# telemetry-r2.net
KiCad netlist of a schematic drawn in EAGLE
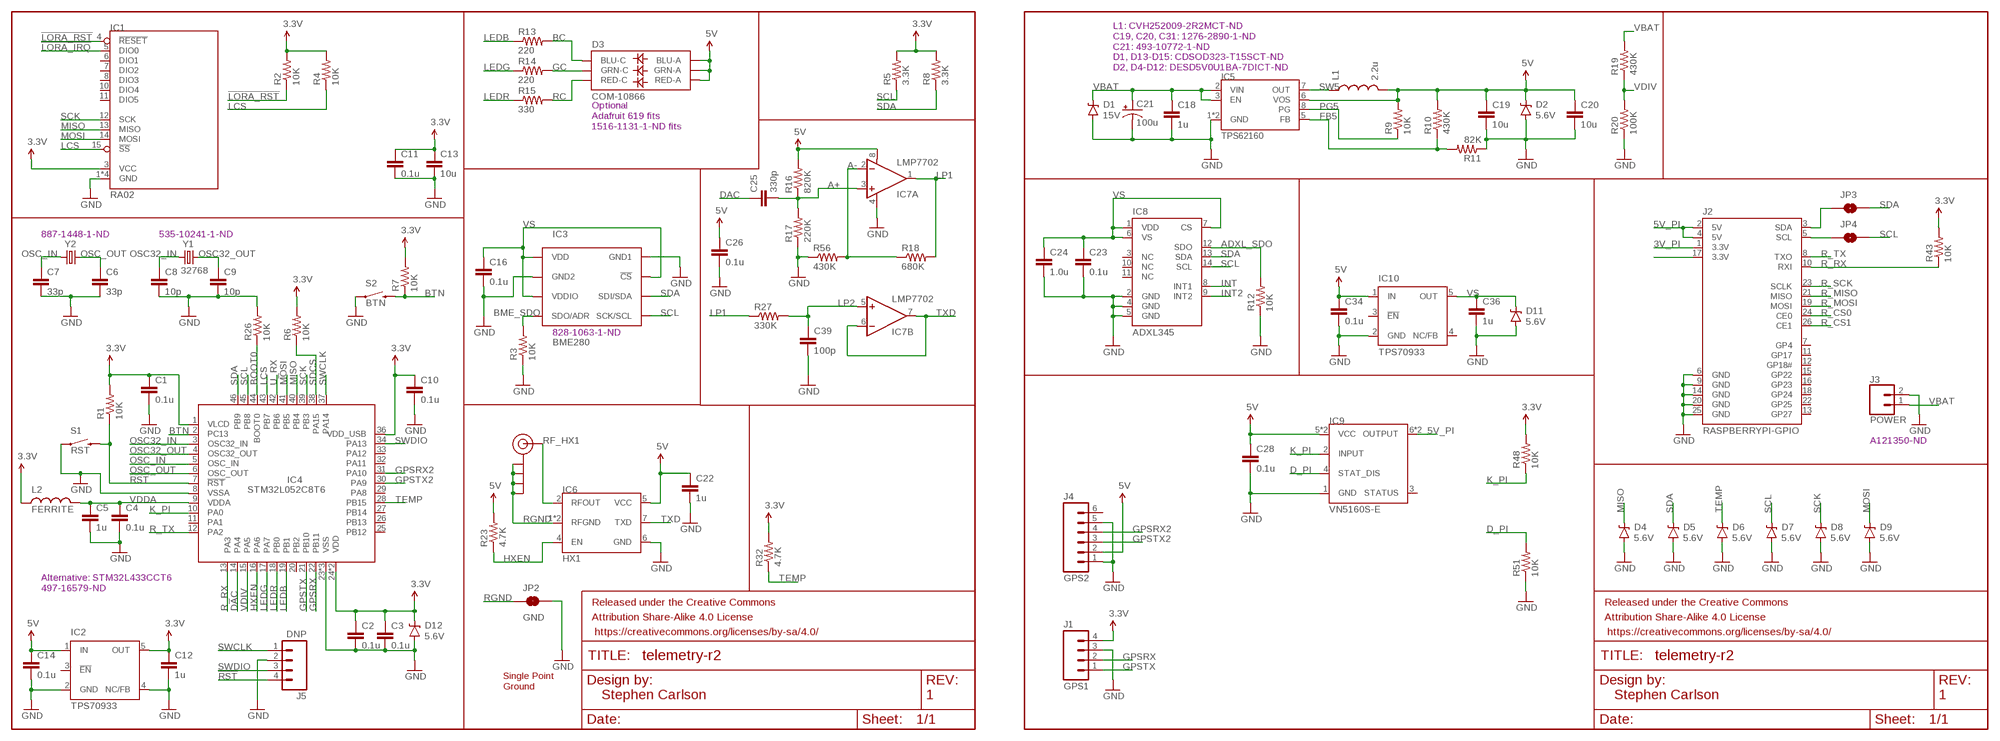
[diagram p0: schematic, sheet 1]

(export (version "E")
  (design (tool "Eeschema 10.0.6"))
  (components
    (comp (ref "C1")
      (value "0.1u")
      (footprint "eagle-import:0805")
      (libsource (lib "eagle-import") (part "CAP0805"))
    )
    (comp (ref "C2")
      (value "0.1u")
      (footprint "eagle-import:0805")
      (libsource (lib "eagle-import") (part "CAP0805"))
    )
    (comp (ref "C3")
      (value "0.1u")
      (footprint "eagle-import:0805")
      (libsource (lib "eagle-import") (part "CAP0805"))
    )
    (comp (ref "C4")
      (value "0.1u")
      (footprint "eagle-import:0805")
      (libsource (lib "eagle-import") (part "CAP0805"))
    )
    (comp (ref "C5")
      (value "1u")
      (footprint "eagle-import:0805")
      (libsource (lib "eagle-import") (part "CAP0805"))
    )
    (comp (ref "C6")
      (value "33p")
      (footprint "eagle-import:0805")
      (libsource (lib "eagle-import") (part "CAP0805"))
    )
    (comp (ref "C7")
      (value "33p")
      (footprint "eagle-import:0805")
      (libsource (lib "eagle-import") (part "CAP0805"))
    )
    (comp (ref "C8")
      (value "10p")
      (footprint "eagle-import:0805")
      (libsource (lib "eagle-import") (part "CAP0805"))
    )
    (comp (ref "C9")
      (value "10p")
      (footprint "eagle-import:0805")
      (libsource (lib "eagle-import") (part "CAP0805"))
    )
    (comp (ref "C10")
      (value "0.1u")
      (footprint "eagle-import:0805")
      (libsource (lib "eagle-import") (part "CAP0805"))
    )
    (comp (ref "C11")
      (value "0.1u")
      (footprint "eagle-import:0805")
      (libsource (lib "eagle-import") (part "CAP0805"))
    )
    (comp (ref "C12")
      (value "1u")
      (footprint "eagle-import:0805")
      (libsource (lib "eagle-import") (part "CAP0805"))
    )
    (comp (ref "C13")
      (value "10u")
      (footprint "eagle-import:0805")
      (libsource (lib "eagle-import") (part "CAP0805"))
    )
    (comp (ref "C14")
      (value "0.1u")
      (footprint "eagle-import:0805")
      (libsource (lib "eagle-import") (part "CAP0805"))
    )
    (comp (ref "C16")
      (value "0.1u")
      (footprint "eagle-import:0805")
      (libsource (lib "eagle-import") (part "CAP0805"))
    )
    (comp (ref "C18")
      (value "1u")
      (footprint "eagle-import:0805")
      (libsource (lib "eagle-import") (part "CAP0805"))
    )
    (comp (ref "C19")
      (value "10u")
      (footprint "eagle-import:0805")
      (libsource (lib "eagle-import") (part "CAP0805"))
    )
    (comp (ref "C20")
      (value "10u")
      (footprint "eagle-import:0805")
      (libsource (lib "eagle-import") (part "CAP0805"))
    )
    (comp (ref "C21")
      (value "100u")
      (footprint "eagle-import:PANASONIC_E")
      (libsource (lib "eagle-import") (part "CAP_POLE"))
    )
    (comp (ref "C22")
      (value "1u")
      (footprint "eagle-import:0805")
      (libsource (lib "eagle-import") (part "CAP0805"))
    )
    (comp (ref "C23")
      (value "0.1u")
      (footprint "eagle-import:0805")
      (libsource (lib "eagle-import") (part "CAP0805"))
    )
    (comp (ref "C24")
      (value "1.0u")
      (footprint "eagle-import:0805")
      (libsource (lib "eagle-import") (part "CAP0805"))
    )
    (comp (ref "C25")
      (value "330p")
      (footprint "eagle-import:0805")
      (libsource (lib "eagle-import") (part "CAP0805"))
    )
    (comp (ref "C26")
      (value "0.1u")
      (footprint "eagle-import:0805")
      (libsource (lib "eagle-import") (part "CAP0805"))
    )
    (comp (ref "C28")
      (value "0.1u")
      (footprint "eagle-import:0805")
      (libsource (lib "eagle-import") (part "CAP0805"))
    )
    (comp (ref "C34")
      (value "0.1u")
      (footprint "eagle-import:0805")
      (libsource (lib "eagle-import") (part "CAP0805"))
    )
    (comp (ref "C36")
      (value "1u")
      (footprint "eagle-import:0805")
      (libsource (lib "eagle-import") (part "CAP0805"))
    )
    (comp (ref "C39")
      (value "100p")
      (footprint "eagle-import:0805")
      (libsource (lib "eagle-import") (part "CAP0805"))
    )
    (comp (ref "D1")
      (value "15V")
      (footprint "eagle-import:SOD-323")
      (libsource (lib "eagle-import") (part "DIODE-ZENER5.6V"))
    )
    (comp (ref "D2")
      (value "5.6V")
      (footprint "eagle-import:SOD-323")
      (libsource (lib "eagle-import") (part "DIODE-ZENER5.6V"))
    )
    (comp (ref "D3")
      (value "COM-10866")
      (footprint "eagle-import:LED-TRICOLOR-5050")
      (libsource (lib "eagle-import") (part "LED-TRICOLOR-5050NO_IC"))
    )
    (comp (ref "D4")
      (value "5.6V")
      (footprint "eagle-import:SOD-323")
      (libsource (lib "eagle-import") (part "DIODE-ZENER5.6V"))
    )
    (comp (ref "D5")
      (value "5.6V")
      (footprint "eagle-import:SOD-323")
      (libsource (lib "eagle-import") (part "DIODE-ZENER5.6V"))
    )
    (comp (ref "D6")
      (value "5.6V")
      (footprint "eagle-import:SOD-323")
      (libsource (lib "eagle-import") (part "DIODE-ZENER5.6V"))
    )
    (comp (ref "D7")
      (value "5.6V")
      (footprint "eagle-import:SOD-323")
      (libsource (lib "eagle-import") (part "DIODE-ZENER5.6V"))
    )
    (comp (ref "D8")
      (value "5.6V")
      (footprint "eagle-import:SOD-323")
      (libsource (lib "eagle-import") (part "DIODE-ZENER5.6V"))
    )
    (comp (ref "D9")
      (value "5.6V")
      (footprint "eagle-import:SOD-323")
      (libsource (lib "eagle-import") (part "DIODE-ZENER5.6V"))
    )
    (comp (ref "D11")
      (value "5.6V")
      (footprint "eagle-import:SOD-323")
      (libsource (lib "eagle-import") (part "DIODE-ZENER5.6V"))
    )
    (comp (ref "D12")
      (value "5.6V")
      (footprint "eagle-import:SOD-323")
      (libsource (lib "eagle-import") (part "DIODE-ZENER5.6V"))
    )
    (comp (ref "FRAME1")
      (value "FRAME-LETTERNO_PACKAGE")
      (footprint "eagle-import:DUMMY")
      (fields (field (name "DESIGNER") "Nobody"))
      (libsource (lib "eagle-import") (part "FRAME-LETTERNO_PACKAGE"))
    )
    (comp (ref "FRAME2")
      (value "FRAME-LETTERNO_PACKAGE")
      (footprint "eagle-import:DUMMY")
      (fields (field (name "DESIGNER") "Nobody"))
      (libsource (lib "eagle-import") (part "FRAME-LETTERNO_PACKAGE"))
    )
    (comp (ref "IC1")
      (value "RA02")
      (footprint "eagle-import:RA02")
      (libsource (lib "eagle-import") (part "RA02"))
    )
    (comp (ref "IC2")
      (value "TPS70933")
      (footprint "eagle-import:SOT23-DBV")
      (fields (field (name "MF") "TEXAS INSTRUMENTS") (field (name "MPN") "TPS77033DBVT"))
      (libsource (lib "eagle-import") (part "TPS77033"))
    )
    (comp (ref "IC3")
      (value "BME280")
      (footprint "eagle-import:BME280_LGA")
      (libsource (lib "eagle-import") (part "BME280"))
    )
    (comp (ref "IC4")
      (value "STM32L052C8T6")
      (footprint "eagle-import:TQFP48")
      (libsource (lib "eagle-import") (part "STM32L07C"))
    )
    (comp (ref "IC5")
      (value "TPS62160")
      (footprint "eagle-import:MSOP8")
      (libsource (lib "eagle-import") (part "TPS62160"))
    )
    (comp (ref "IC6")
      (value "HX1")
      (footprint "eagle-import:HX1")
      (libsource (lib "eagle-import") (part "HX1"))
    )
    (comp (ref "IC7")
      (value "LMP7702")
      (footprint "eagle-import:SO08")
      (libsource (lib "eagle-import") (part "OPAMP-DUALU"))
    )
    (comp (ref "IC8")
      (value "ADXL345")
      (footprint "eagle-import:LGA14")
      (libsource (lib "eagle-import") (part "ADXL345"))
    )
    (comp (ref "IC9")
      (value "VN5160S-E")
      (footprint "eagle-import:SO8")
      (libsource (lib "eagle-import") (part "VN5160S-E"))
    )
    (comp (ref "IC10")
      (value "TPS70933")
      (footprint "eagle-import:SOT23-DBV")
      (fields (field (name "MF") "TEXAS INSTRUMENTS") (field (name "MPN") "TPS77033DBVT"))
      (libsource (lib "eagle-import") (part "TPS77033"))
    )
    (comp (ref "J1")
      (value "GPS1")
      (footprint "eagle-import:1X04")
      (libsource (lib "eagle-import") (part "M04PTH"))
    )
    (comp (ref "J2")
      (value "RASPBERRYPI-GPIO")
      (footprint "eagle-import:2X13-PI")
      (libsource (lib "eagle-import") (part "RASPBERRYPI-GPIO"))
    )
    (comp (ref "J3")
      (value "POWER")
      (footprint "eagle-import:1X02_SCREW")
      (libsource (lib "eagle-import") (part "1X02"))
    )
    (comp (ref "J4")
      (value "GPS2")
      (footprint "eagle-import:1X06-1MM")
      (libsource (lib "eagle-import") (part "M06SMD-1MM"))
    )
    (comp (ref "J5")
      (value "DNP")
      (footprint "eagle-import:1X04_LOCK")
      (libsource (lib "eagle-import") (part "M04LOCK"))
    )
    (comp (ref "J6")
      (value "SMA_EDGE")
      (footprint "eagle-import:SMA-EDGE")
      (libsource (lib "eagle-import") (part "SMA_EDGE"))
    )
    (comp (ref "JP2")
      (value "GND")
      (footprint "eagle-import:PAD-JUMPER-2-NC_BY_TRACE_YES_SILK")
      (libsource (lib "eagle-import") (part "JUMPER-PAD-2-NC_BY_TRACE"))
    )
    (comp (ref "JP3")
      (value "SDA")
      (footprint "eagle-import:SMT-JUMPER_2_NO_SILK")
      (libsource (lib "eagle-import") (part "JUMPER-SMT_2_NO_SILK"))
    )
    (comp (ref "JP4")
      (value "SCL")
      (footprint "eagle-import:SMT-JUMPER_2_NO_SILK")
      (libsource (lib "eagle-import") (part "JUMPER-SMT_2_NO_SILK"))
    )
    (comp (ref "L1")
      (value "2.2u")
      (footprint "eagle-import:1008")
      (libsource (lib "eagle-import") (part "INDUCTOR1008"))
    )
    (comp (ref "L2")
      (value "FERRITE")
      (footprint "eagle-import:1206")
      (libsource (lib "eagle-import") (part "INDUCTOR1206"))
    )
    (comp (ref "R1")
      (value "10K")
      (footprint "eagle-import:0805")
      (libsource (lib "eagle-import") (part "RESISTOR0805-RES"))
    )
    (comp (ref "R2")
      (value "10K")
      (footprint "eagle-import:0805")
      (libsource (lib "eagle-import") (part "RESISTOR0805-RES"))
    )
    (comp (ref "R3")
      (value "10K")
      (footprint "eagle-import:0805")
      (libsource (lib "eagle-import") (part "RESISTOR0805-RES"))
    )
    (comp (ref "R4")
      (value "10K")
      (footprint "eagle-import:0805")
      (libsource (lib "eagle-import") (part "RESISTOR0805-RES"))
    )
    (comp (ref "R5")
      (value "3.3K")
      (footprint "eagle-import:0805")
      (libsource (lib "eagle-import") (part "RESISTOR0805-RES"))
    )
    (comp (ref "R6")
      (value "10K")
      (footprint "eagle-import:0805")
      (libsource (lib "eagle-import") (part "RESISTOR0805-RES"))
    )
    (comp (ref "R7")
      (value "10K")
      (footprint "eagle-import:0805")
      (libsource (lib "eagle-import") (part "RESISTOR0805-RES"))
    )
    (comp (ref "R8")
      (value "3.3K")
      (footprint "eagle-import:0805")
      (libsource (lib "eagle-import") (part "RESISTOR0805-RES"))
    )
    (comp (ref "R9")
      (value "10K")
      (footprint "eagle-import:0805")
      (libsource (lib "eagle-import") (part "RESISTOR0805-RES"))
    )
    (comp (ref "R10")
      (value "430K")
      (footprint "eagle-import:0805")
      (libsource (lib "eagle-import") (part "RESISTOR0805-RES"))
    )
    (comp (ref "R11")
      (value "82K")
      (footprint "eagle-import:0805")
      (libsource (lib "eagle-import") (part "RESISTOR0805-RES"))
    )
    (comp (ref "R12")
      (value "10K")
      (footprint "eagle-import:0805")
      (libsource (lib "eagle-import") (part "RESISTOR0805-RES"))
    )
    (comp (ref "R13")
      (value "220")
      (footprint "eagle-import:0805")
      (libsource (lib "eagle-import") (part "RESISTOR0805-RES"))
    )
    (comp (ref "R14")
      (value "220")
      (footprint "eagle-import:0805")
      (libsource (lib "eagle-import") (part "RESISTOR0805-RES"))
    )
    (comp (ref "R15")
      (value "330")
      (footprint "eagle-import:0805")
      (libsource (lib "eagle-import") (part "RESISTOR0805-RES"))
    )
    (comp (ref "R16")
      (value "820K")
      (footprint "eagle-import:0805")
      (libsource (lib "eagle-import") (part "RESISTOR0805-RES"))
    )
    (comp (ref "R17")
      (value "220K")
      (footprint "eagle-import:0805")
      (libsource (lib "eagle-import") (part "RESISTOR0805-RES"))
    )
    (comp (ref "R18")
      (value "680K")
      (footprint "eagle-import:0805")
      (libsource (lib "eagle-import") (part "RESISTOR0805-RES"))
    )
    (comp (ref "R19")
      (value "430K")
      (footprint "eagle-import:0805")
      (libsource (lib "eagle-import") (part "RESISTOR0805-RES"))
    )
    (comp (ref "R20")
      (value "100K")
      (footprint "eagle-import:0805")
      (libsource (lib "eagle-import") (part "RESISTOR0805-RES"))
    )
    (comp (ref "R23")
      (value "4.7K")
      (footprint "eagle-import:0805")
      (libsource (lib "eagle-import") (part "RESISTOR0805-RES"))
    )
    (comp (ref "R26")
      (value "10K")
      (footprint "eagle-import:0805")
      (libsource (lib "eagle-import") (part "RESISTOR0805-RES"))
    )
    (comp (ref "R27")
      (value "330K")
      (footprint "eagle-import:0805")
      (libsource (lib "eagle-import") (part "RESISTOR0805-RES"))
    )
    (comp (ref "R32")
      (value "4.7K")
      (footprint "eagle-import:0805")
      (libsource (lib "eagle-import") (part "RESISTOR0805-RES"))
    )
    (comp (ref "R43")
      (value "10K")
      (footprint "eagle-import:0805")
      (libsource (lib "eagle-import") (part "RESISTOR0805-RES"))
    )
    (comp (ref "R48")
      (value "10K")
      (footprint "eagle-import:0805")
      (libsource (lib "eagle-import") (part "RESISTOR0805-RES"))
    )
    (comp (ref "R51")
      (value "10K")
      (footprint "eagle-import:0805")
      (libsource (lib "eagle-import") (part "RESISTOR0805-RES"))
    )
    (comp (ref "R56")
      (value "430K")
      (footprint "eagle-import:0805")
      (libsource (lib "eagle-import") (part "RESISTOR0805-RES"))
    )
    (comp (ref "S1")
      (value "RST")
      (footprint "eagle-import:TACTILE-PTH-THIN")
      (libsource (lib "eagle-import") (part "SWITCH"))
    )
    (comp (ref "S2")
      (value "BTN")
      (footprint "eagle-import:TACTILE-PTH-THIN")
      (libsource (lib "eagle-import") (part "SWITCH"))
    )
    (comp (ref "Y1")
      (value "32768")
      (footprint "eagle-import:ABS25")
      (libsource (lib "eagle-import") (part "CRYSTAL"))
    )
    (comp (ref "Y2")
      (value "8M")
      (footprint "eagle-import:CRYSTAL-TXC-7A")
      (libsource (lib "eagle-import") (part "CRYSTALTXC-7A"))
    )
  )
  (nets
    (net (code "1") (name "/3V_PI") (class "Default")
      (node (ref "J2") (pin "1") (pinfunction "3.3V_1") (pintype "power_in"))
    )
    (net (code "2") (name "/5V_PI") (class "Default")
      (node (ref "IC9") (pin "6") (pinfunction "OUTPUT_6") (pintype "passive"))
      (node (ref "IC9") (pin "7") (pinfunction "OUTPUT_7") (pintype "passive"))
      (node (ref "J2") (pin "2") (pinfunction "5V_2") (pintype "power_in"))
      (node (ref "J2") (pin "4") (pinfunction "5V_4") (pintype "power_in"))
    )
    (net (code "3") (name "/A+") (class "Default")
      (node (ref "C25") (pin "2") (pinfunction "2_2") (pintype "passive"))
      (node (ref "IC7") (pin "3") (pinfunction "+IN_3") (pintype "input"))
      (node (ref "R16") (pin "1") (pinfunction "1_1") (pintype "passive"))
      (node (ref "R17") (pin "2") (pinfunction "2_2") (pintype "passive"))
    )
    (net (code "4") (name "/A-") (class "Default")
      (node (ref "IC7") (pin "2") (pinfunction "-IN_2") (pintype "input"))
      (node (ref "R18") (pin "1") (pinfunction "1_1") (pintype "passive"))
      (node (ref "R56") (pin "2") (pinfunction "2_2") (pintype "passive"))
    )
    (net (code "5") (name "/ADXL_SDO") (class "Default")
      (node (ref "IC8") (pin "12") (pinfunction "SDO_12") (pintype "bidirectional"))
      (node (ref "R12") (pin "2") (pinfunction "2_2") (pintype "passive"))
    )
    (net (code "6") (name "/BC") (class "Default")
      (node (ref "D3") (pin "4") (pinfunction "BLU-C_4") (pintype "bidirectional"))
      (node (ref "R13") (pin "2") (pinfunction "2_2") (pintype "passive"))
    )
    (net (code "7") (name "/BME_SDO") (class "Default")
      (node (ref "IC3") (pin "P$5") (pinfunction "SDO/ADR_P$5") (pintype "bidirectional"))
      (node (ref "R3") (pin "2") (pinfunction "2_2") (pintype "passive"))
    )
    (net (code "8") (name "/BOOT0") (class "Default")
      (node (ref "IC4") (pin "44") (pinfunction "BOOT0_44") (pintype "input"))
      (node (ref "R26") (pin "1") (pinfunction "1_1") (pintype "passive"))
    )
    (net (code "9") (name "/BTN") (class "Default")
      (node (ref "IC4") (pin "2") (pinfunction "PC13_2") (pintype "bidirectional"))
      (node (ref "R7") (pin "1") (pinfunction "1_1") (pintype "passive"))
      (node (ref "S2") (pin "2") (pinfunction "2_2") (pintype "passive"))
    )
    (net (code "10") (name "/DAC") (class "Default")
      (node (ref "C25") (pin "1") (pinfunction "1_1") (pintype "passive"))
      (node (ref "IC4") (pin "14") (pinfunction "PA4_14") (pintype "bidirectional"))
    )
    (net (code "11") (name "/D_PI") (class "Default")
      (node (ref "IC9") (pin "4") (pinfunction "STAT_DIS_4") (pintype "input"))
      (node (ref "R51") (pin "2") (pinfunction "2_2") (pintype "passive"))
    )
    (net (code "12") (name "/FB5") (class "Default")
      (node (ref "IC5") (pin "5") (pinfunction "FB_5") (pintype "input"))
      (node (ref "R10") (pin "1") (pinfunction "1_1") (pintype "passive"))
      (node (ref "R11") (pin "2") (pinfunction "2_2") (pintype "passive"))
    )
    (net (code "13") (name "/GC") (class "Default")
      (node (ref "D3") (pin "6") (pinfunction "GRN-C_6") (pintype "bidirectional"))
      (node (ref "R14") (pin "2") (pinfunction "2_2") (pintype "passive"))
    )
    (net (code "14") (name "/GPSRX") (class "Default")
      (node (ref "IC4") (pin "22") (pinfunction "PB11_22") (pintype "bidirectional"))
      (node (ref "J1") (pin "2") (pinfunction "2_2") (pintype "passive"))
    )
    (net (code "15") (name "/GPSRX2") (class "Default")
      (node (ref "IC4") (pin "31") (pinfunction "PA10_31") (pintype "bidirectional"))
      (node (ref "J4") (pin "4") (pinfunction "4_4") (pintype "passive"))
    )
    (net (code "16") (name "/GPSTX") (class "Default")
      (node (ref "IC4") (pin "21") (pinfunction "PB10_21") (pintype "bidirectional"))
      (node (ref "J1") (pin "1") (pinfunction "1_1") (pintype "passive"))
    )
    (net (code "17") (name "/GPSTX2") (class "Default")
      (node (ref "IC4") (pin "30") (pinfunction "PA9_30") (pintype "bidirectional"))
      (node (ref "J4") (pin "3") (pinfunction "3_3") (pintype "passive"))
    )
    (net (code "18") (name "/HXEN") (class "Default")
      (node (ref "IC4") (pin "16") (pinfunction "PA6_16") (pintype "bidirectional"))
      (node (ref "IC6") (pin "4") (pinfunction "EN_4") (pintype "input"))
      (node (ref "R23") (pin "1") (pinfunction "1_1") (pintype "passive"))
    )
    (net (code "19") (name "/INT") (class "Default")
      (node (ref "IC8") (pin "8") (pinfunction "INT1_8") (pintype "bidirectional"))
    )
    (net (code "20") (name "/INT2") (class "Default")
      (node (ref "IC8") (pin "9") (pinfunction "INT2_9") (pintype "bidirectional"))
    )
    (net (code "21") (name "/K_PI") (class "Default")
      (node (ref "IC4") (pin "10") (pinfunction "PA0_10") (pintype "bidirectional"))
      (node (ref "IC9") (pin "2") (pinfunction "INPUT_2") (pintype "input"))
      (node (ref "R48") (pin "1") (pinfunction "1_1") (pintype "passive"))
    )
    (net (code "22") (name "/LCS") (class "Default")
      (node (ref "IC1") (pin "15") (pinfunction "~{SS}_15") (pintype "input"))
      (node (ref "IC4") (pin "43") (pinfunction "PB7_43") (pintype "bidirectional"))
      (node (ref "R4") (pin "1") (pinfunction "1_1") (pintype "passive"))
    )
    (net (code "23") (name "/LEDB") (class "Default")
      (node (ref "IC4") (pin "19") (pinfunction "PB1_19") (pintype "bidirectional"))
      (node (ref "R13") (pin "1") (pinfunction "1_1") (pintype "passive"))
    )
    (net (code "24") (name "/LEDG") (class "Default")
      (node (ref "IC4") (pin "17") (pinfunction "PA7_17") (pintype "bidirectional"))
      (node (ref "R14") (pin "1") (pinfunction "1_1") (pintype "passive"))
    )
    (net (code "25") (name "/LEDR") (class "Default")
      (node (ref "IC4") (pin "18") (pinfunction "PB0_18") (pintype "bidirectional"))
      (node (ref "R15") (pin "1") (pinfunction "1_1") (pintype "passive"))
    )
    (net (code "26") (name "/LP1") (class "Default")
      (node (ref "IC7") (pin "1") (pinfunction "OUT_1") (pintype "output"))
      (node (ref "R18") (pin "2") (pinfunction "2_2") (pintype "passive"))
      (node (ref "R27") (pin "1") (pinfunction "1_1") (pintype "passive"))
    )
    (net (code "27") (name "/LP2") (class "Default")
      (node (ref "C39") (pin "1") (pinfunction "1_1") (pintype "passive"))
      (node (ref "IC7") (pin "5") (pinfunction "+IN_5") (pintype "input"))
      (node (ref "R27") (pin "2") (pinfunction "2_2") (pintype "passive"))
    )
    (net (code "28") (name "/MISO") (class "Default")
      (node (ref "D4") (pin "C") (pinfunction "C_C") (pintype "passive"))
      (node (ref "IC1") (pin "13") (pinfunction "MISO_13") (pintype "output"))
      (node (ref "IC4") (pin "40") (pinfunction "PB4_40") (pintype "bidirectional"))
    )
    (net (code "29") (name "/MOSI") (class "Default")
      (node (ref "D9") (pin "C") (pinfunction "C_C") (pintype "passive"))
      (node (ref "IC1") (pin "14") (pinfunction "MOSI_14") (pintype "input"))
      (node (ref "IC4") (pin "41") (pinfunction "PB5_41") (pintype "bidirectional"))
    )
    (net (code "30") (name "/OSC32_IN") (class "Default")
      (node (ref "C8") (pin "1") (pinfunction "1_1") (pintype "passive"))
      (node (ref "IC4") (pin "3") (pinfunction "OSC32_IN_3") (pintype "bidirectional"))
      (node (ref "Y1") (pin "1") (pinfunction "1_1") (pintype "passive"))
    )
    (net (code "31") (name "/OSC32_OUT") (class "Default")
      (node (ref "C9") (pin "1") (pinfunction "1_1") (pintype "passive"))
      (node (ref "IC4") (pin "4") (pinfunction "OSC32_OUT_4") (pintype "bidirectional"))
      (node (ref "Y1") (pin "4") (pinfunction "2_4") (pintype "passive"))
    )
    (net (code "32") (name "/OSC_IN") (class "Default")
      (node (ref "C7") (pin "1") (pinfunction "1_1") (pintype "passive"))
      (node (ref "IC4") (pin "5") (pinfunction "OSC_IN_5") (pintype "bidirectional"))
      (node (ref "Y2") (pin "P$1") (pinfunction "1_P$1") (pintype "passive"))
    )
    (net (code "33") (name "/OSC_OUT") (class "Default")
      (node (ref "C6") (pin "1") (pinfunction "1_1") (pintype "passive"))
      (node (ref "IC4") (pin "6") (pinfunction "OSC_OUT_6") (pintype "bidirectional"))
      (node (ref "Y2") (pin "P$2") (pinfunction "2_P$2") (pintype "passive"))
    )
    (net (code "34") (name "/PG5") (class "Default")
      (node (ref "IC5") (pin "8") (pinfunction "PG_8") (pintype "open_collector"))
      (node (ref "R9") (pin "1") (pinfunction "1_1") (pintype "passive"))
    )
    (net (code "35") (name "/RC") (class "Default")
      (node (ref "D3") (pin "5") (pinfunction "RED-C_5") (pintype "bidirectional"))
      (node (ref "R15") (pin "2") (pinfunction "2_2") (pintype "passive"))
    )
    (net (code "36") (name "/RF_HX1") (class "Default")
      (node (ref "IC6") (pin "2") (pinfunction "RFOUT_2") (pintype "output"))
      (node (ref "J6") (pin "SIG") (pinfunction "SIGNAL_SIG") (pintype "bidirectional"))
    )
    (net (code "37") (name "/RGND") (class "Default")
      (node (ref "IC6") (pin "1") (pinfunction "RFGND_1") (pintype "power_in"))
      (node (ref "IC6") (pin "3") (pinfunction "RFGND_3") (pintype "power_in"))
      (node (ref "J6") (pin "GND@0") (pinfunction "GND_GND@0") (pintype "bidirectional"))
      (node (ref "J6") (pin "GND@1") (pinfunction "GND_GND@1") (pintype "bidirectional"))
      (node (ref "J6") (pin "GND@2") (pinfunction "GND_GND@2") (pintype "bidirectional"))
      (node (ref "J6") (pin "GND@3") (pinfunction "GND_GND@3") (pintype "bidirectional"))
      (node (ref "JP2") (pin "1") (pinfunction "1_1") (pintype "passive"))
    )
    (net (code "38") (name "/R_CS0") (class "Default")
      (node (ref "J2") (pin "24") (pinfunction "CE0_24") (pintype "output"))
    )
    (net (code "39") (name "/R_CS1") (class "Default")
      (node (ref "J2") (pin "26") (pinfunction "CE1_26") (pintype "output"))
    )
    (net (code "40") (name "/R_MISO") (class "Default")
      (node (ref "J2") (pin "21") (pinfunction "MISO_21") (pintype "input"))
    )
    (net (code "41") (name "/R_MOSI") (class "Default")
      (node (ref "J2") (pin "19") (pinfunction "MOSI_19") (pintype "output"))
    )
    (net (code "42") (name "/R_RX") (class "Default")
      (node (ref "IC4") (pin "13") (pinfunction "PA3_13") (pintype "bidirectional"))
      (node (ref "J2") (pin "10") (pinfunction "RXI_10") (pintype "input"))
      (node (ref "R43") (pin "1") (pinfunction "1_1") (pintype "passive"))
    )
    (net (code "43") (name "/R_SCK") (class "Default")
      (node (ref "J2") (pin "23") (pinfunction "SCLK_23") (pintype "output"))
    )
    (net (code "44") (name "/R_TX") (class "Default")
      (node (ref "IC4") (pin "12") (pinfunction "PA2_12") (pintype "bidirectional"))
      (node (ref "J2") (pin "8") (pinfunction "TXO_8") (pintype "output"))
    )
    (net (code "45") (name "/SCK") (class "Default")
      (node (ref "D8") (pin "C") (pinfunction "C_C") (pintype "passive"))
      (node (ref "IC1") (pin "12") (pinfunction "SCK_12") (pintype "input"))
      (node (ref "IC4") (pin "39") (pinfunction "PB3_39") (pintype "bidirectional"))
    )
    (net (code "46") (name "/SCL") (class "Default")
      (node (ref "D7") (pin "C") (pinfunction "C_C") (pintype "passive"))
      (node (ref "IC3") (pin "P$4") (pinfunction "SCK/SCL_P$4") (pintype "bidirectional"))
      (node (ref "IC4") (pin "45") (pinfunction "PB8_45") (pintype "bidirectional"))
      (node (ref "IC8") (pin "14") (pinfunction "SCL_14") (pintype "bidirectional"))
      (node (ref "JP4") (pin "2") (pinfunction "2_2") (pintype "passive"))
      (node (ref "R5") (pin "1") (pinfunction "1_1") (pintype "passive"))
    )
    (net (code "47") (name "/SDA") (class "Default")
      (node (ref "D5") (pin "C") (pinfunction "C_C") (pintype "passive"))
      (node (ref "IC3") (pin "P$3") (pinfunction "SDI/SDA_P$3") (pintype "bidirectional"))
      (node (ref "IC4") (pin "46") (pinfunction "PB9_46") (pintype "bidirectional"))
      (node (ref "IC8") (pin "13") (pinfunction "SDA_13") (pintype "bidirectional"))
      (node (ref "JP3") (pin "2") (pinfunction "2_2") (pintype "passive"))
      (node (ref "R8") (pin "1") (pinfunction "1_1") (pintype "passive"))
    )
    (net (code "48") (name "/SDCS") (class "Default")
      (node (ref "IC4") (pin "38") (pinfunction "PA15_38") (pintype "bidirectional"))
      (node (ref "R6") (pin "1") (pinfunction "1_1") (pintype "passive"))
    )
    (net (code "49") (name "/SW5") (class "Default")
      (node (ref "IC5") (pin "7") (pinfunction "OUT_7") (pintype "output"))
      (node (ref "L1") (pin "1") (pinfunction "1_1") (pintype "passive"))
    )
    (net (code "50") (name "/SWCLK") (class "Default")
      (node (ref "IC4") (pin "37") (pinfunction "PA14_37") (pintype "bidirectional"))
      (node (ref "J5") (pin "1") (pinfunction "1_1") (pintype "passive"))
    )
    (net (code "51") (name "/SWDIO") (class "Default")
      (node (ref "IC4") (pin "34") (pinfunction "PA13_34") (pintype "bidirectional"))
      (node (ref "J5") (pin "3") (pinfunction "3_3") (pintype "passive"))
    )
    (net (code "52") (name "/TEMP") (class "Default")
      (node (ref "D6") (pin "C") (pinfunction "C_C") (pintype "passive"))
      (node (ref "IC4") (pin "28") (pinfunction "PB15_28") (pintype "bidirectional"))
      (node (ref "R32") (pin "1") (pinfunction "1_1") (pintype "passive"))
    )
    (net (code "53") (name "/TXD") (class "Default")
      (node (ref "IC6") (pin "7") (pinfunction "TXD_7") (pintype "input"))
      (node (ref "IC7") (pin "6") (pinfunction "-IN_6") (pintype "input"))
      (node (ref "IC7") (pin "7") (pinfunction "OUT_7") (pintype "output"))
    )
    (net (code "54") (name "/U_RX") (class "Default")
      (node (ref "IC4") (pin "42") (pinfunction "PB6_42") (pintype "bidirectional"))
    )
    (net (code "55") (name "/VBAT") (class "Default")
      (node (ref "C18") (pin "1") (pinfunction "1_1") (pintype "passive"))
      (node (ref "C21") (pin "+") (pinfunction "+_+") (pintype "passive"))
      (node (ref "D1") (pin "C") (pinfunction "C_C") (pintype "passive"))
      (node (ref "IC5") (pin "2") (pinfunction "VIN_2") (pintype "power_in"))
      (node (ref "IC5") (pin "3") (pinfunction "EN_3") (pintype "input"))
      (node (ref "J3") (pin "1") (pinfunction "1_1") (pintype "passive"))
      (node (ref "R19") (pin "2") (pinfunction "2_2") (pintype "passive"))
    )
    (net (code "56") (name "/VDDA") (class "Default")
      (node (ref "C4") (pin "1") (pinfunction "1_1") (pintype "passive"))
      (node (ref "C5") (pin "1") (pinfunction "1_1") (pintype "passive"))
      (node (ref "IC4") (pin "9") (pinfunction "VDDA_9") (pintype "power_in"))
      (node (ref "L2") (pin "2") (pinfunction "2_2") (pintype "passive"))
    )
    (net (code "57") (name "/VDIV") (class "Default")
      (node (ref "IC4") (pin "15") (pinfunction "PA5_15") (pintype "bidirectional"))
      (node (ref "R19") (pin "1") (pinfunction "1_1") (pintype "passive"))
      (node (ref "R20") (pin "2") (pinfunction "2_2") (pintype "passive"))
    )
    (net (code "58") (name "/VS") (class "Default")
      (node (ref "C16") (pin "1") (pinfunction "1_1") (pintype "passive"))
      (node (ref "C23") (pin "1") (pinfunction "1_1") (pintype "passive"))
      (node (ref "C24") (pin "1") (pinfunction "1_1") (pintype "passive"))
      (node (ref "C36") (pin "1") (pinfunction "1_1") (pintype "passive"))
      (node (ref "D11") (pin "C") (pinfunction "C_C") (pintype "passive"))
      (node (ref "IC10") (pin "5") (pinfunction "OUT_5") (pintype "passive"))
      (node (ref "IC3") (pin "P$2") (pinfunction "~{CS}_P$2") (pintype "bidirectional"))
      (node (ref "IC3") (pin "P$6") (pinfunction "VDDIO_P$6") (pintype "bidirectional"))
      (node (ref "IC3") (pin "P$8") (pinfunction "VDD_P$8") (pintype "bidirectional"))
      (node (ref "IC8") (pin "1") (pinfunction "VDD_1") (pintype "bidirectional"))
      (node (ref "IC8") (pin "6") (pinfunction "VS_6") (pintype "bidirectional"))
      (node (ref "IC8") (pin "7") (pinfunction "CS_7") (pintype "bidirectional"))
    )
    (net (code "59") (name "/~{LORA_IRQ}") (class "Default")
      (node (ref "IC1") (pin "5") (pinfunction "DIO0_5") (pintype "bidirectional"))
    )
    (net (code "60") (name "/~{LORA_RST}") (class "Default")
      (node (ref "IC1") (pin "4") (pinfunction "~{RESET}_4") (pintype "input"))
      (node (ref "R2") (pin "1") (pinfunction "1_1") (pintype "passive"))
    )
    (net (code "61") (name "/~{RST}") (class "Default")
      (node (ref "IC4") (pin "7") (pinfunction "~{RST}_7") (pintype "input"))
      (node (ref "J5") (pin "4") (pinfunction "4_4") (pintype "passive"))
      (node (ref "R1") (pin "1") (pinfunction "1_1") (pintype "passive"))
      (node (ref "S1") (pin "2") (pinfunction "2_2") (pintype "passive"))
    )
    (net (code "62") (name "3.3V") (class "Default")
      (node (ref "C1") (pin "1") (pinfunction "1_1") (pintype "passive"))
      (node (ref "C10") (pin "1") (pinfunction "1_1") (pintype "passive"))
      (node (ref "C11") (pin "1") (pinfunction "1_1") (pintype "passive"))
      (node (ref "C12") (pin "1") (pinfunction "1_1") (pintype "passive"))
      (node (ref "C13") (pin "1") (pinfunction "1_1") (pintype "passive"))
      (node (ref "C2") (pin "1") (pinfunction "1_1") (pintype "passive"))
      (node (ref "C3") (pin "1") (pinfunction "1_1") (pintype "passive"))
      (node (ref "D12") (pin "C") (pinfunction "C_C") (pintype "passive"))
      (node (ref "IC1") (pin "3") (pinfunction "VCC_3") (pintype "power_in"))
      (node (ref "IC2") (pin "5") (pinfunction "OUT_5") (pintype "passive"))
      (node (ref "IC4") (pin "1") (pinfunction "VLCD_1") (pintype "power_in"))
      (node (ref "IC4") (pin "24") (pinfunction "VDD_24") (pintype "power_in"))
      (node (ref "IC4") (pin "36") (pinfunction "VDD_USB_36") (pintype "power_in"))
      (node (ref "IC4") (pin "48") (pinfunction "VDD_48") (pintype "power_in"))
      (node (ref "J1") (pin "4") (pinfunction "4_4") (pintype "passive"))
      (node (ref "L2") (pin "1") (pinfunction "1_1") (pintype "passive"))
      (node (ref "R1") (pin "2") (pinfunction "2_2") (pintype "passive"))
      (node (ref "R2") (pin "2") (pinfunction "2_2") (pintype "passive"))
      (node (ref "R32") (pin "2") (pinfunction "2_2") (pintype "passive"))
      (node (ref "R4") (pin "2") (pinfunction "2_2") (pintype "passive"))
      (node (ref "R43") (pin "2") (pinfunction "2_2") (pintype "passive"))
      (node (ref "R48") (pin "2") (pinfunction "2_2") (pintype "passive"))
      (node (ref "R5") (pin "2") (pinfunction "2_2") (pintype "passive"))
      (node (ref "R6") (pin "2") (pinfunction "2_2") (pintype "passive"))
      (node (ref "R7") (pin "2") (pinfunction "2_2") (pintype "passive"))
      (node (ref "R8") (pin "2") (pinfunction "2_2") (pintype "passive"))
    )
    (net (code "63") (name "5V") (class "Default")
      (node (ref "C14") (pin "1") (pinfunction "1_1") (pintype "passive"))
      (node (ref "C19") (pin "1") (pinfunction "1_1") (pintype "passive"))
      (node (ref "C20") (pin "1") (pinfunction "1_1") (pintype "passive"))
      (node (ref "C22") (pin "1") (pinfunction "1_1") (pintype "passive"))
      (node (ref "C26") (pin "1") (pinfunction "1_1") (pintype "passive"))
      (node (ref "C28") (pin "1") (pinfunction "1_1") (pintype "passive"))
      (node (ref "C34") (pin "1") (pinfunction "1_1") (pintype "passive"))
      (node (ref "D2") (pin "C") (pinfunction "C_C") (pintype "passive"))
      (node (ref "D3") (pin "1") (pinfunction "GRN-A_1") (pintype "bidirectional"))
      (node (ref "D3") (pin "2") (pinfunction "RED-A_2") (pintype "bidirectional"))
      (node (ref "D3") (pin "3") (pinfunction "BLU-A_3") (pintype "bidirectional"))
      (node (ref "IC10") (pin "1") (pinfunction "IN_1") (pintype "input"))
      (node (ref "IC2") (pin "1") (pinfunction "IN_1") (pintype "input"))
      (node (ref "IC5") (pin "6") (pinfunction "VOS_6") (pintype "input"))
      (node (ref "IC6") (pin "5") (pinfunction "VCC_5") (pintype "power_in"))
      (node (ref "IC7") (pin "8") (pinfunction "V+_8") (pintype "power_in"))
      (node (ref "IC9") (pin "5") (pinfunction "VCC_5") (pintype "power_in"))
      (node (ref "IC9") (pin "8") (pinfunction "VCC_8") (pintype "power_in"))
      (node (ref "J4") (pin "2") (pinfunction "2_2") (pintype "passive"))
      (node (ref "L1") (pin "2") (pinfunction "2_2") (pintype "passive"))
      (node (ref "R10") (pin "2") (pinfunction "2_2") (pintype "passive"))
      (node (ref "R16") (pin "2") (pinfunction "2_2") (pintype "passive"))
      (node (ref "R23") (pin "2") (pinfunction "2_2") (pintype "passive"))
      (node (ref "R9") (pin "2") (pinfunction "2_2") (pintype "passive"))
    )
    (net (code "64") (name "GND") (class "Default")
      (node (ref "C1") (pin "2") (pinfunction "2_2") (pintype "passive"))
      (node (ref "C10") (pin "2") (pinfunction "2_2") (pintype "passive"))
      (node (ref "C11") (pin "2") (pinfunction "2_2") (pintype "passive"))
      (node (ref "C12") (pin "2") (pinfunction "2_2") (pintype "passive"))
      (node (ref "C13") (pin "2") (pinfunction "2_2") (pintype "passive"))
      (node (ref "C14") (pin "2") (pinfunction "2_2") (pintype "passive"))
      (node (ref "C16") (pin "2") (pinfunction "2_2") (pintype "passive"))
      (node (ref "C18") (pin "2") (pinfunction "2_2") (pintype "passive"))
      (node (ref "C19") (pin "2") (pinfunction "2_2") (pintype "passive"))
      (node (ref "C2") (pin "2") (pinfunction "2_2") (pintype "passive"))
      (node (ref "C20") (pin "2") (pinfunction "2_2") (pintype "passive"))
      (node (ref "C21") (pin "-") (pinfunction "-_-") (pintype "passive"))
      (node (ref "C22") (pin "2") (pinfunction "2_2") (pintype "passive"))
      (node (ref "C23") (pin "2") (pinfunction "2_2") (pintype "passive"))
      (node (ref "C24") (pin "2") (pinfunction "2_2") (pintype "passive"))
      (node (ref "C26") (pin "2") (pinfunction "2_2") (pintype "passive"))
      (node (ref "C28") (pin "2") (pinfunction "2_2") (pintype "passive"))
      (node (ref "C3") (pin "2") (pinfunction "2_2") (pintype "passive"))
      (node (ref "C34") (pin "2") (pinfunction "2_2") (pintype "passive"))
      (node (ref "C36") (pin "2") (pinfunction "2_2") (pintype "passive"))
      (node (ref "C39") (pin "2") (pinfunction "2_2") (pintype "passive"))
      (node (ref "C4") (pin "2") (pinfunction "2_2") (pintype "passive"))
      (node (ref "C5") (pin "2") (pinfunction "2_2") (pintype "passive"))
      (node (ref "C6") (pin "2") (pinfunction "2_2") (pintype "passive"))
      (node (ref "C7") (pin "2") (pinfunction "2_2") (pintype "passive"))
      (node (ref "C8") (pin "2") (pinfunction "2_2") (pintype "passive"))
      (node (ref "C9") (pin "2") (pinfunction "2_2") (pintype "passive"))
      (node (ref "D1") (pin "A") (pinfunction "A_A") (pintype "passive"))
      (node (ref "D11") (pin "A") (pinfunction "A_A") (pintype "passive"))
      (node (ref "D12") (pin "A") (pinfunction "A_A") (pintype "passive"))
      (node (ref "D2") (pin "A") (pinfunction "A_A") (pintype "passive"))
      (node (ref "D4") (pin "A") (pinfunction "A_A") (pintype "passive"))
      (node (ref "D5") (pin "A") (pinfunction "A_A") (pintype "passive"))
      (node (ref "D6") (pin "A") (pinfunction "A_A") (pintype "passive"))
      (node (ref "D7") (pin "A") (pinfunction "A_A") (pintype "passive"))
      (node (ref "D8") (pin "A") (pinfunction "A_A") (pintype "passive"))
      (node (ref "D9") (pin "A") (pinfunction "A_A") (pintype "passive"))
      (node (ref "IC1") (pin "1") (pinfunction "GND_1") (pintype "power_in"))
      (node (ref "IC1") (pin "16") (pinfunction "GND_16") (pintype "power_in"))
      (node (ref "IC1") (pin "2") (pinfunction "GND_2") (pintype "power_in"))
      (node (ref "IC1") (pin "9") (pinfunction "GND_9") (pintype "power_in"))
      (node (ref "IC10") (pin "2") (pinfunction "GND_2") (pintype "power_in"))
      (node (ref "IC2") (pin "2") (pinfunction "GND_2") (pintype "power_in"))
      (node (ref "IC2") (pin "4") (pinfunction "NC/FB_4") (pintype "passive"))
      (node (ref "IC3") (pin "P$1") (pinfunction "GND1_P$1") (pintype "bidirectional"))
      (node (ref "IC3") (pin "P$7") (pinfunction "GND2_P$7") (pintype "bidirectional"))
      (node (ref "IC4") (pin "23") (pinfunction "VSS_23") (pintype "power_in"))
      (node (ref "IC4") (pin "35") (pinfunction "VSS_35") (pintype "power_in"))
      (node (ref "IC4") (pin "47") (pinfunction "VSS_47") (pintype "power_in"))
      (node (ref "IC4") (pin "8") (pinfunction "VSSA_8") (pintype "power_in"))
      (node (ref "IC5") (pin "1") (pinfunction "GND_1") (pintype "power_in"))
      (node (ref "IC5") (pin "4") (pinfunction "GND_4") (pintype "power_in"))
      (node (ref "IC6") (pin "6") (pinfunction "GND_6") (pintype "power_in"))
      (node (ref "IC7") (pin "4") (pinfunction "V-_4") (pintype "power_in"))
      (node (ref "IC8") (pin "2") (pinfunction "GND_2") (pintype "bidirectional"))
      (node (ref "IC8") (pin "4") (pinfunction "GND_4") (pintype "bidirectional"))
      (node (ref "IC8") (pin "5") (pinfunction "GND_5") (pintype "bidirectional"))
      (node (ref "IC9") (pin "1") (pinfunction "GND_1") (pintype "power_in"))
      (node (ref "J1") (pin "3") (pinfunction "3_3") (pintype "passive"))
      (node (ref "J2") (pin "14") (pinfunction "GND_14") (pintype "power_in"))
      (node (ref "J2") (pin "20") (pinfunction "GND_20") (pintype "power_in"))
      (node (ref "J2") (pin "25") (pinfunction "GND_25") (pintype "power_in"))
      (node (ref "J2") (pin "6") (pinfunction "GND_6") (pintype "power_in"))
      (node (ref "J2") (pin "9") (pinfunction "GND_9") (pintype "power_in"))
      (node (ref "J3") (pin "2") (pinfunction "2_2") (pintype "passive"))
      (node (ref "J4") (pin "1") (pinfunction "1_1") (pintype "passive"))
      (node (ref "J4") (pin "5") (pinfunction "5_5") (pintype "passive"))
      (node (ref "J5") (pin "2") (pinfunction "2_2") (pintype "passive"))
      (node (ref "JP2") (pin "2") (pinfunction "2_2") (pintype "passive"))
      (node (ref "R11") (pin "1") (pinfunction "1_1") (pintype "passive"))
      (node (ref "R12") (pin "1") (pinfunction "1_1") (pintype "passive"))
      (node (ref "R17") (pin "1") (pinfunction "1_1") (pintype "passive"))
      (node (ref "R20") (pin "1") (pinfunction "1_1") (pintype "passive"))
      (node (ref "R26") (pin "2") (pinfunction "2_2") (pintype "passive"))
      (node (ref "R3") (pin "1") (pinfunction "1_1") (pintype "passive"))
      (node (ref "R51") (pin "1") (pinfunction "1_1") (pintype "passive"))
      (node (ref "R56") (pin "1") (pinfunction "1_1") (pintype "passive"))
      (node (ref "S1") (pin "1") (pinfunction "1_1") (pintype "passive"))
      (node (ref "S2") (pin "1") (pinfunction "1_1") (pintype "passive"))
    )
    (net (code "65") (name "Net-(J2-SCL)") (class "Default")
      (node (ref "J2") (pin "5") (pinfunction "SCL_5") (pintype "bidirectional"))
      (node (ref "JP4") (pin "1") (pinfunction "1_1") (pintype "passive"))
    )
    (net (code "66") (name "Net-(J2-SDA)") (class "Default")
      (node (ref "J2") (pin "3") (pinfunction "SDA_3") (pintype "bidirectional"))
      (node (ref "JP3") (pin "1") (pinfunction "1_1") (pintype "passive"))
    )
    (net (code "67") (name "unconnected-(IC1-DIO1-Pad6)") (class "Default")
      (node (ref "IC1") (pin "6") (pinfunction "DIO1_6") (pintype "bidirectional"))
    )
    (net (code "68") (name "unconnected-(IC1-DIO2-Pad7)") (class "Default")
      (node (ref "IC1") (pin "7") (pinfunction "DIO2_7") (pintype "bidirectional"))
    )
    (net (code "69") (name "unconnected-(IC1-DIO3-Pad8)") (class "Default")
      (node (ref "IC1") (pin "8") (pinfunction "DIO3_8") (pintype "bidirectional"))
    )
    (net (code "70") (name "unconnected-(IC1-DIO4-Pad10)") (class "Default")
      (node (ref "IC1") (pin "10") (pinfunction "DIO4_10") (pintype "bidirectional"))
    )
    (net (code "71") (name "unconnected-(IC1-DIO5-Pad11)") (class "Default")
      (node (ref "IC1") (pin "11") (pinfunction "DIO5_11") (pintype "bidirectional"))
    )
    (net (code "72") (name "unconnected-(IC2-~{EN}-Pad3)") (class "Default")
      (node (ref "IC2") (pin "3") (pinfunction "~{EN}_3") (pintype "input"))
    )
    (net (code "73") (name "unconnected-(IC4-PA1-Pad11)") (class "Default")
      (node (ref "IC4") (pin "11") (pinfunction "PA1_11") (pintype "bidirectional"))
    )
    (net (code "74") (name "unconnected-(IC4-PA8-Pad29)") (class "Default")
      (node (ref "IC4") (pin "29") (pinfunction "PA8_29") (pintype "bidirectional"))
    )
    (net (code "75") (name "unconnected-(IC4-PA11-Pad32)") (class "Default")
      (node (ref "IC4") (pin "32") (pinfunction "PA11_32") (pintype "bidirectional"))
    )
    (net (code "76") (name "unconnected-(IC4-PA12-Pad33)") (class "Default")
      (node (ref "IC4") (pin "33") (pinfunction "PA12_33") (pintype "bidirectional"))
    )
    (net (code "77") (name "unconnected-(IC4-PB2-Pad20)") (class "Default")
      (node (ref "IC4") (pin "20") (pinfunction "PB2_20") (pintype "bidirectional"))
    )
    (net (code "78") (name "unconnected-(IC4-PB12-Pad25)") (class "Default")
      (node (ref "IC4") (pin "25") (pinfunction "PB12_25") (pintype "bidirectional"))
    )
    (net (code "79") (name "unconnected-(IC4-PB13-Pad26)") (class "Default")
      (node (ref "IC4") (pin "26") (pinfunction "PB13_26") (pintype "bidirectional"))
    )
    (net (code "80") (name "unconnected-(IC4-PB14-Pad27)") (class "Default")
      (node (ref "IC4") (pin "27") (pinfunction "PB14_27") (pintype "bidirectional"))
    )
    (net (code "81") (name "unconnected-(IC8-NC-Pad3)") (class "Default")
      (node (ref "IC8") (pin "3") (pinfunction "NC_3") (pintype "bidirectional"))
    )
    (net (code "82") (name "unconnected-(IC8-NC-Pad10)") (class "Default")
      (node (ref "IC8") (pin "10") (pinfunction "NC_10") (pintype "bidirectional"))
    )
    (net (code "83") (name "unconnected-(IC8-NC-Pad11)") (class "Default")
      (node (ref "IC8") (pin "11") (pinfunction "NC_11") (pintype "bidirectional"))
    )
    (net (code "84") (name "unconnected-(IC9-STATUS-Pad3)") (class "Default")
      (node (ref "IC9") (pin "3") (pinfunction "STATUS_3") (pintype "open_collector"))
    )
    (net (code "85") (name "unconnected-(IC10-NC{slash}FB-Pad4)") (class "Default")
      (node (ref "IC10") (pin "4") (pinfunction "NC/FB_4") (pintype "passive"))
    )
    (net (code "86") (name "unconnected-(IC10-~{EN}-Pad3)") (class "Default")
      (node (ref "IC10") (pin "3") (pinfunction "~{EN}_3") (pintype "input"))
    )
    (net (code "87") (name "unconnected-(J2-3.3V-Pad17)") (class "Default")
      (node (ref "J2") (pin "17") (pinfunction "3.3V_17") (pintype "power_in"))
    )
    (net (code "88") (name "unconnected-(J2-GP4-Pad7)") (class "Default")
      (node (ref "J2") (pin "7") (pinfunction "GP4_7") (pintype "bidirectional"))
    )
    (net (code "89") (name "unconnected-(J2-GP17-Pad11)") (class "Default")
      (node (ref "J2") (pin "11") (pinfunction "GP17_11") (pintype "bidirectional"))
    )
    (net (code "90") (name "unconnected-(J2-GP18#-Pad12)") (class "Default")
      (node (ref "J2") (pin "12") (pinfunction "GP18#_12") (pintype "bidirectional"))
    )
    (net (code "91") (name "unconnected-(J2-GP22-Pad15)") (class "Default")
      (node (ref "J2") (pin "15") (pinfunction "GP22_15") (pintype "bidirectional"))
    )
    (net (code "92") (name "unconnected-(J2-GP23-Pad16)") (class "Default")
      (node (ref "J2") (pin "16") (pinfunction "GP23_16") (pintype "bidirectional"))
    )
    (net (code "93") (name "unconnected-(J2-GP24-Pad18)") (class "Default")
      (node (ref "J2") (pin "18") (pinfunction "GP24_18") (pintype "bidirectional"))
    )
    (net (code "94") (name "unconnected-(J2-GP25-Pad22)") (class "Default")
      (node (ref "J2") (pin "22") (pinfunction "GP25_22") (pintype "bidirectional"))
    )
    (net (code "95") (name "unconnected-(J2-GP27-Pad13)") (class "Default")
      (node (ref "J2") (pin "13") (pinfunction "GP27_13") (pintype "bidirectional"))
    )
    (net (code "96") (name "unconnected-(J4-Pad6)") (class "Default")
      (node (ref "J4") (pin "6") (pinfunction "6_6") (pintype "passive"))
    )
  )
)
